# 3d_gyroscope.net
KiCad netlist of a schematic drawn in Altium Designer
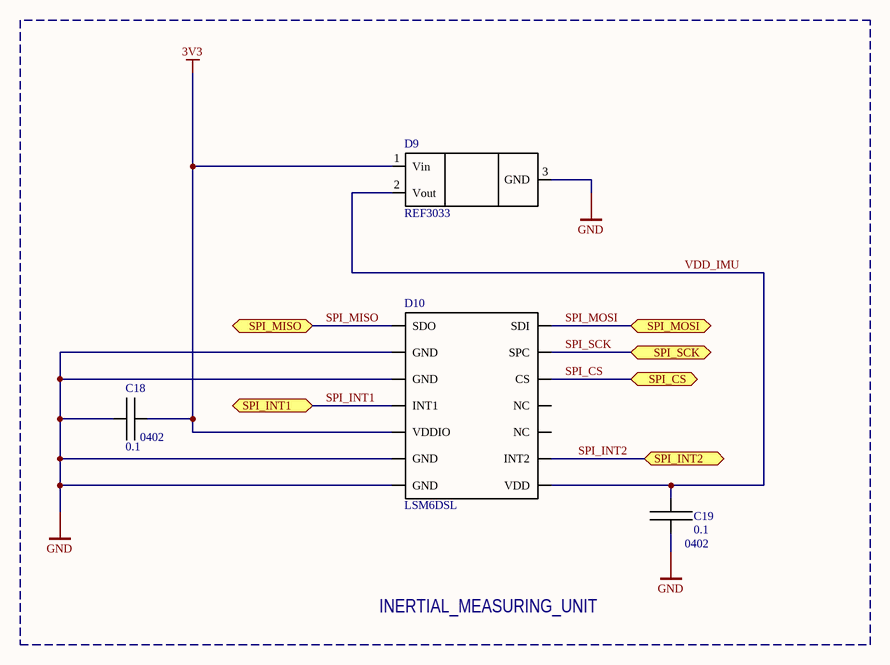
[diagram p0: 3d_gyroscope.SchDoc]

(export (version "E")
  (design (tool "Eeschema 10.0.6"))
  (components
    (comp (ref "C18")
      (value "0.1")
      (footprint "Mylibrary:SMD_0402_C")
      (libsource (lib "Mylibrary") (part "Capacitor"))
    )
    (comp (ref "C19")
      (value "0.1")
      (footprint "Mylibrary:SMD_0402_C")
      (libsource (lib "Mylibrary") (part "Capacitor"))
    )
    (comp (ref "D9")
      (value "REF3033")
      (footprint "Mylibrary:SOT23-3L")
      (description "VOLTAGE STATIC SOURCE 3.3V")
      (libsource (lib "Mylibrary") (part "REF3033"))
    )
    (comp (ref "D10")
      (value "LSM6DSL")
      (footprint "Mylibrary:LGA14C50P5X4_300X250X86")
      (description "3D accelerometer and 3D gyroscope")
      (libsource (lib "Mylibrary") (part "LSM6DSL"))
    )
  )
  (nets
    (net (code "1") (name "/SPI_CS") (class "Default")
      (node (ref "D10") (pin "12") (pinfunction "CS_12") (pintype "passive"))
    )
    (net (code "2") (name "/SPI_INT1") (class "Default")
      (node (ref "D10") (pin "4") (pinfunction "INT1_4") (pintype "passive"))
    )
    (net (code "3") (name "/SPI_INT2") (class "Default")
      (node (ref "D10") (pin "9") (pinfunction "INT2_9") (pintype "passive"))
    )
    (net (code "4") (name "/SPI_MISO") (class "Default")
      (node (ref "D10") (pin "1") (pinfunction "SDO_1") (pintype "passive"))
    )
    (net (code "5") (name "/SPI_MOSI") (class "Default")
      (node (ref "D10") (pin "14") (pinfunction "SDI_14") (pintype "passive"))
    )
    (net (code "6") (name "/SPI_SCK") (class "Default")
      (node (ref "D10") (pin "13") (pinfunction "SPC_13") (pintype "passive"))
    )
    (net (code "7") (name "/VDD_IMU") (class "Default")
      (node (ref "C19") (pin "2") (pinfunction "2_2") (pintype "passive"))
      (node (ref "D10") (pin "8") (pinfunction "VDD_8") (pintype "passive"))
      (node (ref "D9") (pin "2") (pinfunction "Vout_2") (pintype "passive"))
    )
    (net (code "8") (name "3V3") (class "Default")
      (node (ref "C18") (pin "2") (pinfunction "2_2") (pintype "passive"))
      (node (ref "D10") (pin "5") (pinfunction "VDDIO_5") (pintype "passive"))
      (node (ref "D9") (pin "1") (pinfunction "Vin_1") (pintype "passive"))
    )
    (net (code "9") (name "GND") (class "Default")
      (node (ref "C18") (pin "1") (pinfunction "1_1") (pintype "passive"))
      (node (ref "C19") (pin "1") (pinfunction "1_1") (pintype "passive"))
      (node (ref "D10") (pin "2") (pinfunction "GND_2") (pintype "passive"))
      (node (ref "D10") (pin "3") (pinfunction "GND_3") (pintype "passive"))
      (node (ref "D10") (pin "6") (pinfunction "GND_6") (pintype "passive"))
      (node (ref "D10") (pin "7") (pinfunction "GND_7") (pintype "passive"))
      (node (ref "D9") (pin "3") (pinfunction "GND_3") (pintype "passive"))
    )
    (net (code "10") (name "unconnected-(D10-NC-Pad10)") (class "Default")
      (node (ref "D10") (pin "10") (pinfunction "NC_10") (pintype "passive"))
    )
    (net (code "11") (name "unconnected-(D10-NC-Pad11)") (class "Default")
      (node (ref "D10") (pin "11") (pinfunction "NC_11") (pintype "passive"))
    )
  )
)
